# btle_board_R0_2.net
KiCad netlist of a schematic drawn in EAGLE
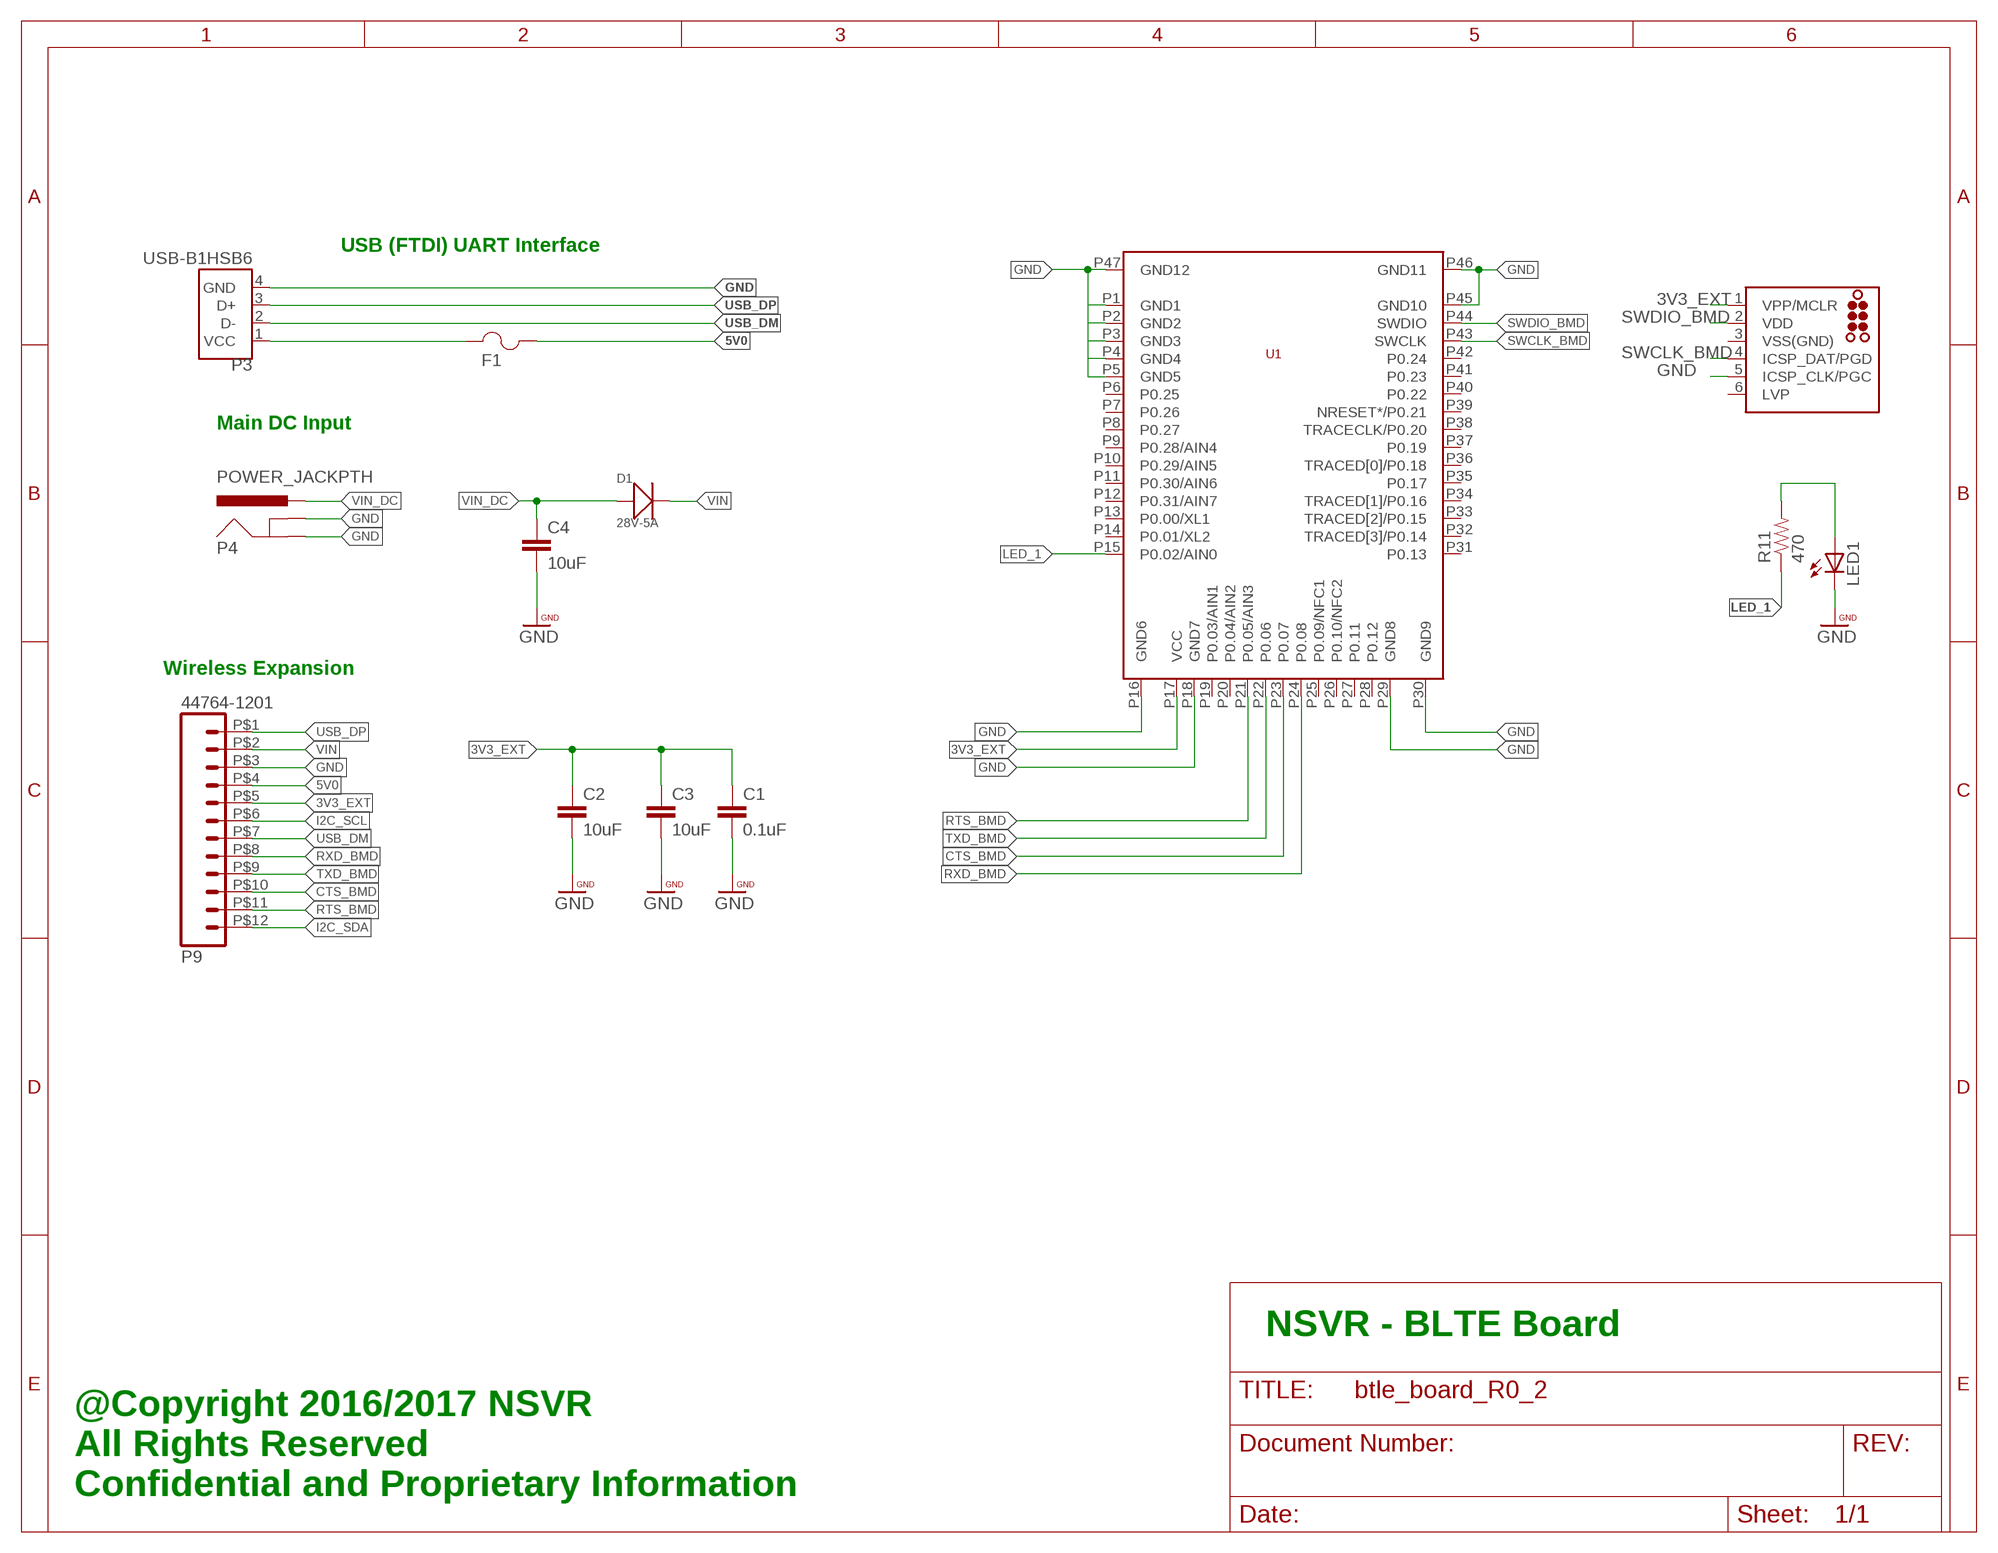
[diagram p0: schematic, sheet 1]

(export (version "E")
  (design (tool "Eeschema 10.0.6"))
  (components
    (comp (ref "C1")
      (value "0.1uF")
      (footprint "eagle-import:0603-CAP")
      (libsource (lib "eagle-import") (part "CAP0603-CAP"))
    )
    (comp (ref "C2")
      (value "10uF")
      (footprint "eagle-import:0603-CAP")
      (libsource (lib "eagle-import") (part "CAP0603-CAP"))
    )
    (comp (ref "C3")
      (value "10uF")
      (footprint "eagle-import:0603-CAP")
      (libsource (lib "eagle-import") (part "CAP0603-CAP"))
    )
    (comp (ref "C4")
      (value "10uF")
      (footprint "eagle-import:0603-CAP")
      (libsource (lib "eagle-import") (part "CAP0603-CAP"))
    )
    (comp (ref "D1")
      (value "28V-5A")
      (footprint "eagle-import:DO-214AA")
      (fields (field (name "MPN") "SS54B"))
      (libsource (lib "eagle-import") (part "SMD-DIODE-SCHOTTKY-28V-5A(DO-214AA)"))
    )
    (comp (ref "F1")
      (value "1206L050YR")
      (footprint "eagle-import:1206LSERIES")
      (fields (field (name "COPYRIGHT") "Copyright C 2015 Accelerated Designs. All rights reserved"))
      (libsource (lib "eagle-import") (part "1206L050YR"))
    )
    (comp (ref "LED1")
      (value "LEDCHIP-LED0603")
      (footprint "eagle-import:CHIP-LED0603")
      (libsource (lib "eagle-import") (part "LEDCHIP-LED0603"))
    )
    (comp (ref "P1")
      (value "TC2030-MCP-NL")
      (footprint "eagle-import:TC2030-MCP-NL")
      (libsource (lib "eagle-import") (part "TC2030-MCP-NL"))
    )
    (comp (ref "P3")
      (value "USB-B1HSB6")
      (footprint "eagle-import:OST_USB-B1HSB6")
      (fields (field (name "MF") "On Shore Technology"))
      (libsource (lib "eagle-import") (part "USB-B1HSB6"))
    )
    (comp (ref "P4")
      (value "POWER_JACKPTH")
      (footprint "eagle-import:POWER_JACK_PTH")
      (libsource (lib "eagle-import") (part "POWER_JACKPTH"))
    )
    (comp (ref "P9")
      (value "44764-1201")
      (footprint "eagle-import:44764-1201")
      (libsource (lib "eagle-import") (part "44764-1201"))
    )
    (comp (ref "R11")
      (value "470")
      (footprint "eagle-import:EIA-0402")
      (libsource (lib "eagle-import") (part "RESISTOR0402-TYP"))
    )
    (comp (ref "U1")
      (value "BMD-300")
      (footprint "eagle-import:BMD-300")
      (libsource (lib "eagle-import") (part "BMD-300"))
    )
  )
  (nets
    (net (code "1") (name "/VSS(GND)") (class "Default")
      (node (ref "P1") (pin "3") (pinfunction "VSS(GND)_3") (pintype "power_in"))
    )
    (net (code "2") (name "3V3_EXT") (class "Default")
      (node (ref "C1") (pin "1") (pinfunction "1_1") (pintype "passive"))
      (node (ref "C2") (pin "1") (pinfunction "1_1") (pintype "passive"))
      (node (ref "C3") (pin "1") (pinfunction "1_1") (pintype "passive"))
      (node (ref "P1") (pin "1") (pinfunction "VPP/MCLR_1") (pintype "passive"))
      (node (ref "P9") (pin "P$5") (pinfunction "5_P$5") (pintype "passive"))
      (node (ref "U1") (pin "P17") (pinfunction "VCC_P17") (pintype "bidirectional"))
    )
    (net (code "3") (name "5V0") (class "Default")
      (node (ref "F1") (pin "2") (pinfunction "2_2") (pintype "passive"))
      (node (ref "P9") (pin "P$4") (pinfunction "4_P$4") (pintype "passive"))
    )
    (net (code "4") (name "CTS_BMD") (class "Default")
      (node (ref "P9") (pin "P$10") (pinfunction "10_P$10") (pintype "passive"))
      (node (ref "U1") (pin "P23") (pinfunction "P0.07_P23") (pintype "bidirectional"))
    )
    (net (code "5") (name "GND") (class "Default")
      (node (ref "C1") (pin "2") (pinfunction "2_2") (pintype "passive"))
      (node (ref "C2") (pin "2") (pinfunction "2_2") (pintype "passive"))
      (node (ref "C3") (pin "2") (pinfunction "2_2") (pintype "passive"))
      (node (ref "C4") (pin "2") (pinfunction "2_2") (pintype "passive"))
      (node (ref "LED1") (pin "C") (pinfunction "C_C") (pintype "passive"))
      (node (ref "P1") (pin "5") (pinfunction "ICSP_CLK/PGC_5") (pintype "output"))
      (node (ref "P3") (pin "4") (pinfunction "GND_4") (pintype "power_in"))
      (node (ref "P4") (pin "GND") (pinfunction "GND_GND") (pintype "bidirectional"))
      (node (ref "P4") (pin "GNDBREAK") (pinfunction "GNDBREAK_GNDBREAK") (pintype "bidirectional"))
      (node (ref "P9") (pin "P$3") (pinfunction "3_P$3") (pintype "passive"))
      (node (ref "U1") (pin "P1") (pinfunction "GND1_P1") (pintype "bidirectional"))
      (node (ref "U1") (pin "P16") (pinfunction "GND6_P16") (pintype "bidirectional"))
      (node (ref "U1") (pin "P18") (pinfunction "GND7_P18") (pintype "bidirectional"))
      (node (ref "U1") (pin "P2") (pinfunction "GND2_P2") (pintype "bidirectional"))
      (node (ref "U1") (pin "P29") (pinfunction "GND8_P29") (pintype "bidirectional"))
      (node (ref "U1") (pin "P3") (pinfunction "GND3_P3") (pintype "bidirectional"))
      (node (ref "U1") (pin "P30") (pinfunction "GND9_P30") (pintype "bidirectional"))
      (node (ref "U1") (pin "P4") (pinfunction "GND4_P4") (pintype "bidirectional"))
      (node (ref "U1") (pin "P45") (pinfunction "GND10_P45") (pintype "bidirectional"))
      (node (ref "U1") (pin "P46") (pinfunction "GND11_P46") (pintype "bidirectional"))
      (node (ref "U1") (pin "P47") (pinfunction "GND12_P47") (pintype "bidirectional"))
      (node (ref "U1") (pin "P5") (pinfunction "GND5_P5") (pintype "bidirectional"))
    )
    (net (code "6") (name "I2C_SCL") (class "Default")
      (node (ref "P9") (pin "P$6") (pinfunction "6_P$6") (pintype "passive"))
    )
    (net (code "7") (name "I2C_SDA") (class "Default")
      (node (ref "P9") (pin "P$12") (pinfunction "12_P$12") (pintype "passive"))
    )
    (net (code "8") (name "LED_1") (class "Default")
      (node (ref "R11") (pin "1") (pinfunction "1_1") (pintype "passive"))
      (node (ref "U1") (pin "P15") (pinfunction "P0.02/AIN0_P15") (pintype "bidirectional"))
    )
    (net (code "9") (name "Net-(LED1-PadA)") (class "Default")
      (node (ref "LED1") (pin "A") (pinfunction "A_A") (pintype "passive"))
      (node (ref "R11") (pin "2") (pinfunction "2_2") (pintype "passive"))
    )
    (net (code "10") (name "Net-(P3-VCC)") (class "Default")
      (node (ref "F1") (pin "1") (pinfunction "1_1") (pintype "passive"))
      (node (ref "P3") (pin "1") (pinfunction "VCC_1") (pintype "power_in"))
    )
    (net (code "11") (name "RTS_BMD") (class "Default")
      (node (ref "P9") (pin "P$11") (pinfunction "11_P$11") (pintype "passive"))
      (node (ref "U1") (pin "P21") (pinfunction "P0.05/AIN3_P21") (pintype "bidirectional"))
    )
    (net (code "12") (name "RXD_BMD") (class "Default")
      (node (ref "P9") (pin "P$8") (pinfunction "8_P$8") (pintype "passive"))
      (node (ref "U1") (pin "P24") (pinfunction "P0.08_P24") (pintype "bidirectional"))
    )
    (net (code "13") (name "SWCLK_BMD") (class "Default")
      (node (ref "P1") (pin "4") (pinfunction "ICSP_DAT/PGD_4") (pintype "bidirectional"))
      (node (ref "U1") (pin "P43") (pinfunction "SWCLK_P43") (pintype "bidirectional"))
    )
    (net (code "14") (name "SWDIO_BMD") (class "Default")
      (node (ref "P1") (pin "2") (pinfunction "VDD_2") (pintype "power_in"))
      (node (ref "U1") (pin "P44") (pinfunction "SWDIO_P44") (pintype "bidirectional"))
    )
    (net (code "15") (name "TXD_BMD") (class "Default")
      (node (ref "P9") (pin "P$9") (pinfunction "9_P$9") (pintype "passive"))
      (node (ref "U1") (pin "P22") (pinfunction "P0.06_P22") (pintype "bidirectional"))
    )
    (net (code "16") (name "USB_DM") (class "Default")
      (node (ref "P3") (pin "2") (pinfunction "D-_2") (pintype "bidirectional"))
      (node (ref "P9") (pin "P$7") (pinfunction "7_P$7") (pintype "passive"))
    )
    (net (code "17") (name "USB_DP") (class "Default")
      (node (ref "P3") (pin "3") (pinfunction "D+_3") (pintype "bidirectional"))
      (node (ref "P9") (pin "P$1") (pinfunction "1_P$1") (pintype "passive"))
    )
    (net (code "18") (name "VIN") (class "Default")
      (node (ref "D1") (pin "-") (pinfunction "-_-") (pintype "passive"))
      (node (ref "P9") (pin "P$2") (pinfunction "2_P$2") (pintype "passive"))
    )
    (net (code "19") (name "VIN_DC") (class "Default")
      (node (ref "C4") (pin "1") (pinfunction "1_1") (pintype "passive"))
      (node (ref "D1") (pin "+") (pinfunction "+_+") (pintype "passive"))
      (node (ref "P4") (pin "PWR") (pinfunction "PWR_PWR") (pintype "bidirectional"))
    )
    (net (code "20") (name "unconnected-(P1-LVP-Pad6)") (class "Default")
      (node (ref "P1") (pin "6") (pinfunction "LVP_6") (pintype "bidirectional"))
    )
    (net (code "21") (name "unconnected-(U1-NRESET*{slash}P0.21-PadP39)") (class "Default")
      (node (ref "U1") (pin "P39") (pinfunction "NRESET*/P0.21_P39") (pintype "bidirectional"))
    )
    (net (code "22") (name "unconnected-(U1-P0.00{slash}XL1-PadP13)") (class "Default")
      (node (ref "U1") (pin "P13") (pinfunction "P0.00/XL1_P13") (pintype "bidirectional"))
    )
    (net (code "23") (name "unconnected-(U1-P0.01{slash}XL2-PadP14)") (class "Default")
      (node (ref "U1") (pin "P14") (pinfunction "P0.01/XL2_P14") (pintype "bidirectional"))
    )
    (net (code "24") (name "unconnected-(U1-P0.03{slash}AIN1-PadP19)") (class "Default")
      (node (ref "U1") (pin "P19") (pinfunction "P0.03/AIN1_P19") (pintype "bidirectional"))
    )
    (net (code "25") (name "unconnected-(U1-P0.04{slash}AIN2-PadP20)") (class "Default")
      (node (ref "U1") (pin "P20") (pinfunction "P0.04/AIN2_P20") (pintype "bidirectional"))
    )
    (net (code "26") (name "unconnected-(U1-P0.09{slash}NFC1-PadP25)") (class "Default")
      (node (ref "U1") (pin "P25") (pinfunction "P0.09/NFC1_P25") (pintype "bidirectional"))
    )
    (net (code "27") (name "unconnected-(U1-P0.10{slash}NFC2-PadP26)") (class "Default")
      (node (ref "U1") (pin "P26") (pinfunction "P0.10/NFC2_P26") (pintype "bidirectional"))
    )
    (net (code "28") (name "unconnected-(U1-P0.11-PadP27)") (class "Default")
      (node (ref "U1") (pin "P27") (pinfunction "P0.11_P27") (pintype "bidirectional"))
    )
    (net (code "29") (name "unconnected-(U1-P0.12-PadP28)") (class "Default")
      (node (ref "U1") (pin "P28") (pinfunction "P0.12_P28") (pintype "bidirectional"))
    )
    (net (code "30") (name "unconnected-(U1-P0.13-PadP31)") (class "Default")
      (node (ref "U1") (pin "P31") (pinfunction "P0.13_P31") (pintype "bidirectional"))
    )
    (net (code "31") (name "unconnected-(U1-P0.17-PadP35)") (class "Default")
      (node (ref "U1") (pin "P35") (pinfunction "P0.17_P35") (pintype "bidirectional"))
    )
    (net (code "32") (name "unconnected-(U1-P0.19-PadP37)") (class "Default")
      (node (ref "U1") (pin "P37") (pinfunction "P0.19_P37") (pintype "bidirectional"))
    )
    (net (code "33") (name "unconnected-(U1-P0.22-PadP40)") (class "Default")
      (node (ref "U1") (pin "P40") (pinfunction "P0.22_P40") (pintype "bidirectional"))
    )
    (net (code "34") (name "unconnected-(U1-P0.23-PadP41)") (class "Default")
      (node (ref "U1") (pin "P41") (pinfunction "P0.23_P41") (pintype "bidirectional"))
    )
    (net (code "35") (name "unconnected-(U1-P0.24-PadP42)") (class "Default")
      (node (ref "U1") (pin "P42") (pinfunction "P0.24_P42") (pintype "bidirectional"))
    )
    (net (code "36") (name "unconnected-(U1-P0.25-PadP6)") (class "Default")
      (node (ref "U1") (pin "P6") (pinfunction "P0.25_P6") (pintype "bidirectional"))
    )
    (net (code "37") (name "unconnected-(U1-P0.26-PadP7)") (class "Default")
      (node (ref "U1") (pin "P7") (pinfunction "P0.26_P7") (pintype "bidirectional"))
    )
    (net (code "38") (name "unconnected-(U1-P0.27-PadP8)") (class "Default")
      (node (ref "U1") (pin "P8") (pinfunction "P0.27_P8") (pintype "bidirectional"))
    )
    (net (code "39") (name "unconnected-(U1-P0.28{slash}AIN4-PadP9)") (class "Default")
      (node (ref "U1") (pin "P9") (pinfunction "P0.28/AIN4_P9") (pintype "bidirectional"))
    )
    (net (code "40") (name "unconnected-(U1-P0.29{slash}AIN5-PadP10)") (class "Default")
      (node (ref "U1") (pin "P10") (pinfunction "P0.29/AIN5_P10") (pintype "bidirectional"))
    )
    (net (code "41") (name "unconnected-(U1-P0.30{slash}AIN6-PadP11)") (class "Default")
      (node (ref "U1") (pin "P11") (pinfunction "P0.30/AIN6_P11") (pintype "bidirectional"))
    )
    (net (code "42") (name "unconnected-(U1-P0.31{slash}AIN7-PadP12)") (class "Default")
      (node (ref "U1") (pin "P12") (pinfunction "P0.31/AIN7_P12") (pintype "bidirectional"))
    )
    (net (code "43") (name "unconnected-(U1-TRACECLK{slash}P0.20-PadP38)") (class "Default")
      (node (ref "U1") (pin "P38") (pinfunction "TRACECLK/P0.20_P38") (pintype "bidirectional"))
    )
    (net (code "44") (name "unconnected-(U1-TRACED[0]{slash}P0.18-PadP36)") (class "Default")
      (node (ref "U1") (pin "P36") (pinfunction "TRACED[0]/P0.18_P36") (pintype "bidirectional"))
    )
    (net (code "45") (name "unconnected-(U1-TRACED[1]{slash}P0.16-PadP34)") (class "Default")
      (node (ref "U1") (pin "P34") (pinfunction "TRACED[1]/P0.16_P34") (pintype "bidirectional"))
    )
    (net (code "46") (name "unconnected-(U1-TRACED[2]{slash}P0.15-PadP33)") (class "Default")
      (node (ref "U1") (pin "P33") (pinfunction "TRACED[2]/P0.15_P33") (pintype "bidirectional"))
    )
    (net (code "47") (name "unconnected-(U1-TRACED[3]{slash}P0.14-PadP32)") (class "Default")
      (node (ref "U1") (pin "P32") (pinfunction "TRACED[3]/P0.14_P32") (pintype "bidirectional"))
    )
  )
)
